# Time4CM4_SIT_module.net
KiCad netlist of a schematic drawn in Altium Designer
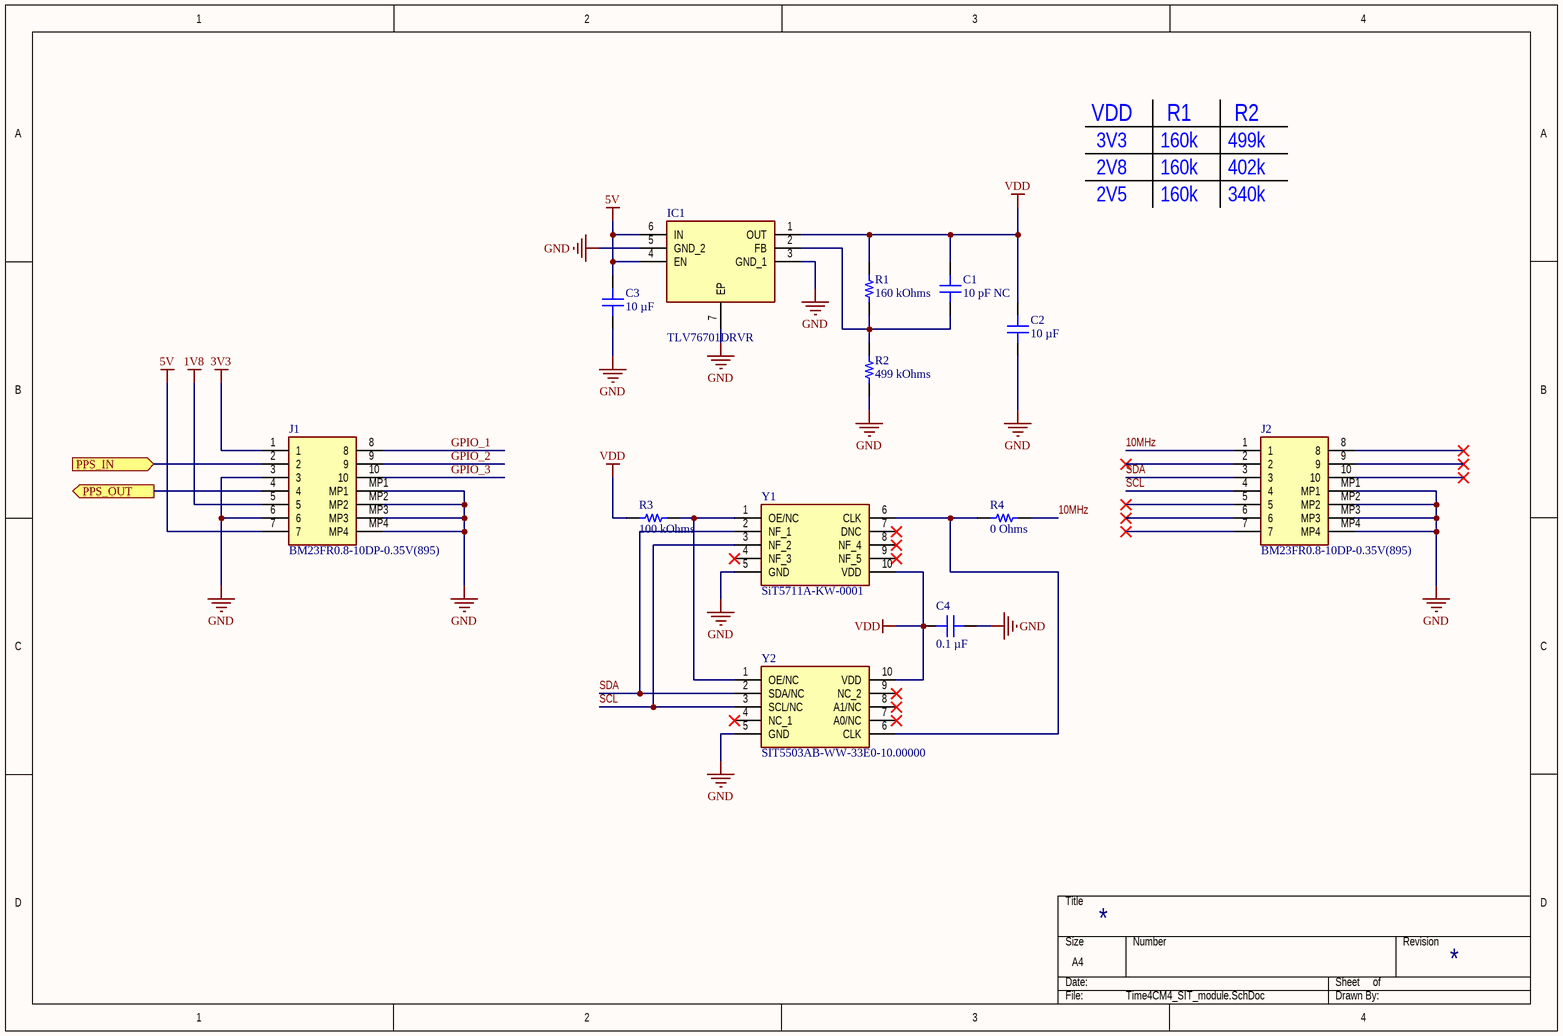
[diagram p0: Time4CM4_SIT_module.SchDoc]

(export (version "E")
  (design (tool "Eeschema 10.0.6"))
  (components
    (comp (ref "C1")
      (value "10 pF NC")
      (footprint "CAP 0402_1005")
      (description "CAP CER 10PF 50V C0G/NPO 0402")
      (fields (field (name "PART NUMBER") "CC0402KRNPO9BN100") (field (name "MANUFACTURER") "Yageo"))
      (libsource (lib "Celestial Altium Library - altium_library") (part "Capacitor"))
    )
    (comp (ref "C2")
      (value "10 µF")
      (footprint "CAP 0603_1608")
      (description "CAP CER 10UF 6.3V X5R 0603")
      (fields (field (name "PART NUMBER") "CC0603MPX5R5BB106") (field (name "MANUFACTURER") "Yageo"))
      (libsource (lib "Celestial Altium Library - altium_library") (part "Capacitor"))
    )
    (comp (ref "C3")
      (value "10 µF")
      (footprint "CAP 0603_1608")
      (description "CAP CER 10UF 6.3V X5R 0603")
      (fields (field (name "PART NUMBER") "CC0603MPX5R5BB106") (field (name "MANUFACTURER") "Yageo"))
      (libsource (lib "Celestial Altium Library - altium_library") (part "Capacitor"))
    )
    (comp (ref "C4")
      (value "0.1 µF")
      (footprint "CAP 0402_1005")
      (description "CAP CER 0.1UF 6.3V X7R 0402")
      (fields (field (name "PART NUMBER") "CC0402KRX7R5BB104") (field (name "MANUFACTURER") "Yageo"))
      (libsource (lib "Celestial Altium Library - altium_library") (part "Capacitor"))
    )
    (comp (ref "IC1")
      (value "TLV76701DRVR")
      (footprint "SamacSys:SON65P200X200X80-7N")
      (description "IC REG LINEAR POS ADJ 1A 6WSON")
      (fields (field (name "MOUSER PART NUMBER") "595-TLV76701DRVR"))
      (libsource (lib "SamacSys") (part "TLV76701DRVR"))
    )
    (comp (ref "J1")
      (value "BM23FR0.8-10DP-0.35V(895)")
      (footprint "SamacSys:BM23FR0810DP035V895")
      (description "Connector")
      (fields
        (field (name "MANUFACTURER_PART_NUMBER") "BM23FR0.8-10DS-0.35V(895)")
        (field (name "MOUSER PART NUMBER") "798-3FR0810DS035V895")
      )
      (libsource (lib "*") (part "BM23FR0.8-10DS-0.35V_895_"))
    )
    (comp (ref "J2")
      (value "BM23FR0.8-10DP-0.35V(895)")
      (footprint "SamacSys:BM23FR0810DP035V895")
      (description "Connector")
      (fields
        (field (name "MANUFACTURER_PART_NUMBER") "BM23FR0.8-10DS-0.35V(895)")
        (field (name "MOUSER PART NUMBER") "798-3FR0810DS035V895")
      )
      (libsource (lib "*") (part "BM23FR0.8-10DS-0.35V_895_"))
    )
    (comp (ref "R1")
      (value "160 kOhms")
      (footprint "YAGEO RES 0402_1005")
      (description "RES 160K OHM 1% 1/16W 0402")
      (fields (field (name "PART NUMBER") "RC0402FR-07160KL") (field (name "MANUFACTURER") "Yageo"))
      (libsource (lib "Celestial Altium Library - altium_library") (part "Resistor"))
    )
    (comp (ref "R2")
      (value "499 kOhms")
      (footprint "YAGEO RES 0402_1005")
      (description "RES 499K OHM 1% 1/16W 0402")
      (fields (field (name "PART NUMBER") "RC0402FR-07499KL") (field (name "MANUFACTURER") "Yageo"))
      (libsource (lib "Celestial Altium Library - altium_library") (part "Resistor"))
    )
    (comp (ref "R3")
      (value "100 kOhms")
      (footprint "YAGEO RES 0402_1005")
      (description "RES 100K OHM 1% 1/16W 0402")
      (fields (field (name "PART NUMBER") "RC0402FR-07100KL") (field (name "MANUFACTURER") "Yageo"))
      (libsource (lib "Celestial Altium Library - altium_library") (part "Resistor"))
    )
    (comp (ref "R4")
      (value "0 Ohms")
      (footprint "YAGEO RES 0402_1005")
      (description "RES 0 OHM JUMPER 1/16W 0402")
      (fields (field (name "PART NUMBER") "RC0402FR-070RL") (field (name "MANUFACTURER") "Yageo"))
      (libsource (lib "Celestial Altium Library - altium_library") (part "Resistor"))
    )
    (comp (ref "Y1")
      (value "SiT5711A-KW-0001")
      (footprint "SamacSys:Emerald_9070_10pins_2022")
      (description "Crystal or Oscillator")
      (libsource (lib "SamacSys") (part "SiT5711A-KW-0001"))
    )
    (comp (ref "Y2")
      (value "SIT5503AB-WW-33E0-10.00000")
      (footprint "SamacSys:Ceramic_QFN_7050_10pins")
      (description "Crystal or Oscillator")
      (libsource (lib "SamacSys") (part "SIT5503AB-WW-33E0-10.00000"))
    )
  )
  (nets
    (net (code "1") (name "/10MHz") (class "Default")
      (node (ref "J2") (pin "1") (pinfunction "1_1") (pintype "passive"))
      (node (ref "R4") (pin "1") (pinfunction "1_1") (pintype "passive"))
    )
    (net (code "2") (name "/GPIO_1") (class "Default")
      (node (ref "J1") (pin "8") (pinfunction "8_8") (pintype "passive"))
    )
    (net (code "3") (name "/GPIO_2") (class "Default")
      (node (ref "J1") (pin "9") (pinfunction "9_9") (pintype "passive"))
    )
    (net (code "4") (name "/GPIO_3") (class "Default")
      (node (ref "J1") (pin "10") (pinfunction "10_10") (pintype "passive"))
    )
    (net (code "5") (name "/PPS_IN") (class "Default")
      (node (ref "J1") (pin "2") (pinfunction "2_2") (pintype "passive"))
    )
    (net (code "6") (name "/PPS_OUT") (class "Default")
      (node (ref "J1") (pin "4") (pinfunction "4_4") (pintype "passive"))
    )
    (net (code "7") (name "/SCL") (class "Default")
      (node (ref "J2") (pin "4") (pinfunction "4_4") (pintype "passive"))
      (node (ref "Y1") (pin "3") (pinfunction "NF_2_3") (pintype "passive"))
      (node (ref "Y2") (pin "3") (pinfunction "SCL/NC_3") (pintype "passive"))
    )
    (net (code "8") (name "/SDA") (class "Default")
      (node (ref "J2") (pin "3") (pinfunction "3_3") (pintype "passive"))
      (node (ref "Y1") (pin "2") (pinfunction "NF_1_2") (pintype "passive"))
      (node (ref "Y2") (pin "2") (pinfunction "SDA/NC_2") (pintype "passive"))
    )
    (net (code "9") (name "1V8") (class "Default")
      (node (ref "J1") (pin "5") (pinfunction "5_5") (pintype "passive"))
    )
    (net (code "10") (name "3V3") (class "Default")
      (node (ref "J1") (pin "1") (pinfunction "1_1") (pintype "passive"))
    )
    (net (code "11") (name "5V") (class "Default")
      (node (ref "C3") (pin "2") (pinfunction "2_2") (pintype "passive"))
      (node (ref "IC1") (pin "4") (pinfunction "EN_4") (pintype "passive"))
      (node (ref "IC1") (pin "6") (pinfunction "IN_6") (pintype "passive"))
      (node (ref "J1") (pin "7") (pinfunction "7_7") (pintype "passive"))
    )
    (net (code "12") (name "GND") (class "Default")
      (node (ref "C2") (pin "1") (pinfunction "1_1") (pintype "passive"))
      (node (ref "C3") (pin "1") (pinfunction "1_1") (pintype "passive"))
      (node (ref "C4") (pin "1") (pinfunction "1_1") (pintype "passive"))
      (node (ref "IC1") (pin "3") (pinfunction "GND_1_3") (pintype "passive"))
      (node (ref "IC1") (pin "5") (pinfunction "GND_2_5") (pintype "passive"))
      (node (ref "IC1") (pin "7") (pinfunction "EP_7") (pintype "passive"))
      (node (ref "J1") (pin "3") (pinfunction "3_3") (pintype "passive"))
      (node (ref "J1") (pin "6") (pinfunction "6_6") (pintype "passive"))
      (node (ref "J1") (pin "MP1") (pinfunction "MP1_MP1") (pintype "passive"))
      (node (ref "J1") (pin "MP2") (pinfunction "MP2_MP2") (pintype "passive"))
      (node (ref "J1") (pin "MP3") (pinfunction "MP3_MP3") (pintype "passive"))
      (node (ref "J1") (pin "MP4") (pinfunction "MP4_MP4") (pintype "passive"))
      (node (ref "J2") (pin "MP1") (pinfunction "MP1_MP1") (pintype "passive"))
      (node (ref "J2") (pin "MP2") (pinfunction "MP2_MP2") (pintype "passive"))
      (node (ref "J2") (pin "MP3") (pinfunction "MP3_MP3") (pintype "passive"))
      (node (ref "J2") (pin "MP4") (pinfunction "MP4_MP4") (pintype "passive"))
      (node (ref "R2") (pin "1") (pinfunction "1_1") (pintype "passive"))
      (node (ref "Y1") (pin "5") (pinfunction "GND_5") (pintype "passive"))
      (node (ref "Y2") (pin "5") (pinfunction "GND_5") (pintype "passive"))
    )
    (net (code "13") (name "Net-(IC1-FB)") (class "Default")
      (node (ref "C1") (pin "1") (pinfunction "1_1") (pintype "passive"))
      (node (ref "IC1") (pin "2") (pinfunction "FB_2") (pintype "passive"))
      (node (ref "R1") (pin "1") (pinfunction "1_1") (pintype "passive"))
      (node (ref "R2") (pin "2") (pinfunction "2_2") (pintype "passive"))
    )
    (net (code "14") (name "Net-(Y1-CLK)") (class "Default")
      (node (ref "R4") (pin "2") (pinfunction "2_2") (pintype "passive"))
      (node (ref "Y1") (pin "6") (pinfunction "CLK_6") (pintype "passive"))
      (node (ref "Y2") (pin "6") (pinfunction "CLK_6") (pintype "passive"))
    )
    (net (code "15") (name "Net-(Y1-OE{slash}NC)") (class "Default")
      (node (ref "R3") (pin "2") (pinfunction "2_2") (pintype "passive"))
      (node (ref "Y1") (pin "1") (pinfunction "OE/NC_1") (pintype "passive"))
      (node (ref "Y2") (pin "1") (pinfunction "OE/NC_1") (pintype "passive"))
    )
    (net (code "16") (name "VDD") (class "Default")
      (node (ref "C1") (pin "2") (pinfunction "2_2") (pintype "passive"))
      (node (ref "C2") (pin "2") (pinfunction "2_2") (pintype "passive"))
      (node (ref "C4") (pin "2") (pinfunction "2_2") (pintype "passive"))
      (node (ref "IC1") (pin "1") (pinfunction "OUT_1") (pintype "passive"))
      (node (ref "R1") (pin "2") (pinfunction "2_2") (pintype "passive"))
      (node (ref "R3") (pin "1") (pinfunction "1_1") (pintype "passive"))
      (node (ref "Y1") (pin "10") (pinfunction "VDD_10") (pintype "passive"))
      (node (ref "Y2") (pin "10") (pinfunction "VDD_10") (pintype "passive"))
    )
    (net (code "17") (name "unconnected-(J2-Pad2)") (class "Default")
      (node (ref "J2") (pin "2") (pinfunction "2_2") (pintype "passive+no_connect"))
    )
    (net (code "18") (name "unconnected-(J2-Pad5)") (class "Default")
      (node (ref "J2") (pin "5") (pinfunction "5_5") (pintype "passive+no_connect"))
    )
    (net (code "19") (name "unconnected-(J2-Pad6)") (class "Default")
      (node (ref "J2") (pin "6") (pinfunction "6_6") (pintype "passive+no_connect"))
    )
    (net (code "20") (name "unconnected-(J2-Pad7)") (class "Default")
      (node (ref "J2") (pin "7") (pinfunction "7_7") (pintype "passive+no_connect"))
    )
    (net (code "21") (name "unconnected-(J2-Pad8)") (class "Default")
      (node (ref "J2") (pin "8") (pinfunction "8_8") (pintype "passive+no_connect"))
    )
    (net (code "22") (name "unconnected-(J2-Pad9)") (class "Default")
      (node (ref "J2") (pin "9") (pinfunction "9_9") (pintype "passive+no_connect"))
    )
    (net (code "23") (name "unconnected-(J2-Pad10)") (class "Default")
      (node (ref "J2") (pin "10") (pinfunction "10_10") (pintype "passive+no_connect"))
    )
    (net (code "24") (name "unconnected-(Y1-DNC-Pad7)") (class "Default")
      (node (ref "Y1") (pin "7") (pinfunction "DNC_7") (pintype "passive+no_connect"))
    )
    (net (code "25") (name "unconnected-(Y1-NF_3-Pad4)") (class "Default")
      (node (ref "Y1") (pin "4") (pinfunction "NF_3_4") (pintype "passive+no_connect"))
    )
    (net (code "26") (name "unconnected-(Y1-NF_4-Pad8)") (class "Default")
      (node (ref "Y1") (pin "8") (pinfunction "NF_4_8") (pintype "passive+no_connect"))
    )
    (net (code "27") (name "unconnected-(Y1-NF_5-Pad9)") (class "Default")
      (node (ref "Y1") (pin "9") (pinfunction "NF_5_9") (pintype "passive+no_connect"))
    )
    (net (code "28") (name "unconnected-(Y2-A0{slash}NC-Pad7)") (class "Default")
      (node (ref "Y2") (pin "7") (pinfunction "A0/NC_7") (pintype "passive+no_connect"))
    )
    (net (code "29") (name "unconnected-(Y2-A1{slash}NC-Pad8)") (class "Default")
      (node (ref "Y2") (pin "8") (pinfunction "A1/NC_8") (pintype "passive+no_connect"))
    )
    (net (code "30") (name "unconnected-(Y2-NC_1-Pad4)") (class "Default")
      (node (ref "Y2") (pin "4") (pinfunction "NC_1_4") (pintype "passive+no_connect"))
    )
    (net (code "31") (name "unconnected-(Y2-NC_2-Pad9)") (class "Default")
      (node (ref "Y2") (pin "9") (pinfunction "NC_2_9") (pintype "passive+no_connect"))
    )
  )
)
